# CH32F103R-R0.net
KiCad netlist of a schematic drawn in Altium Designer
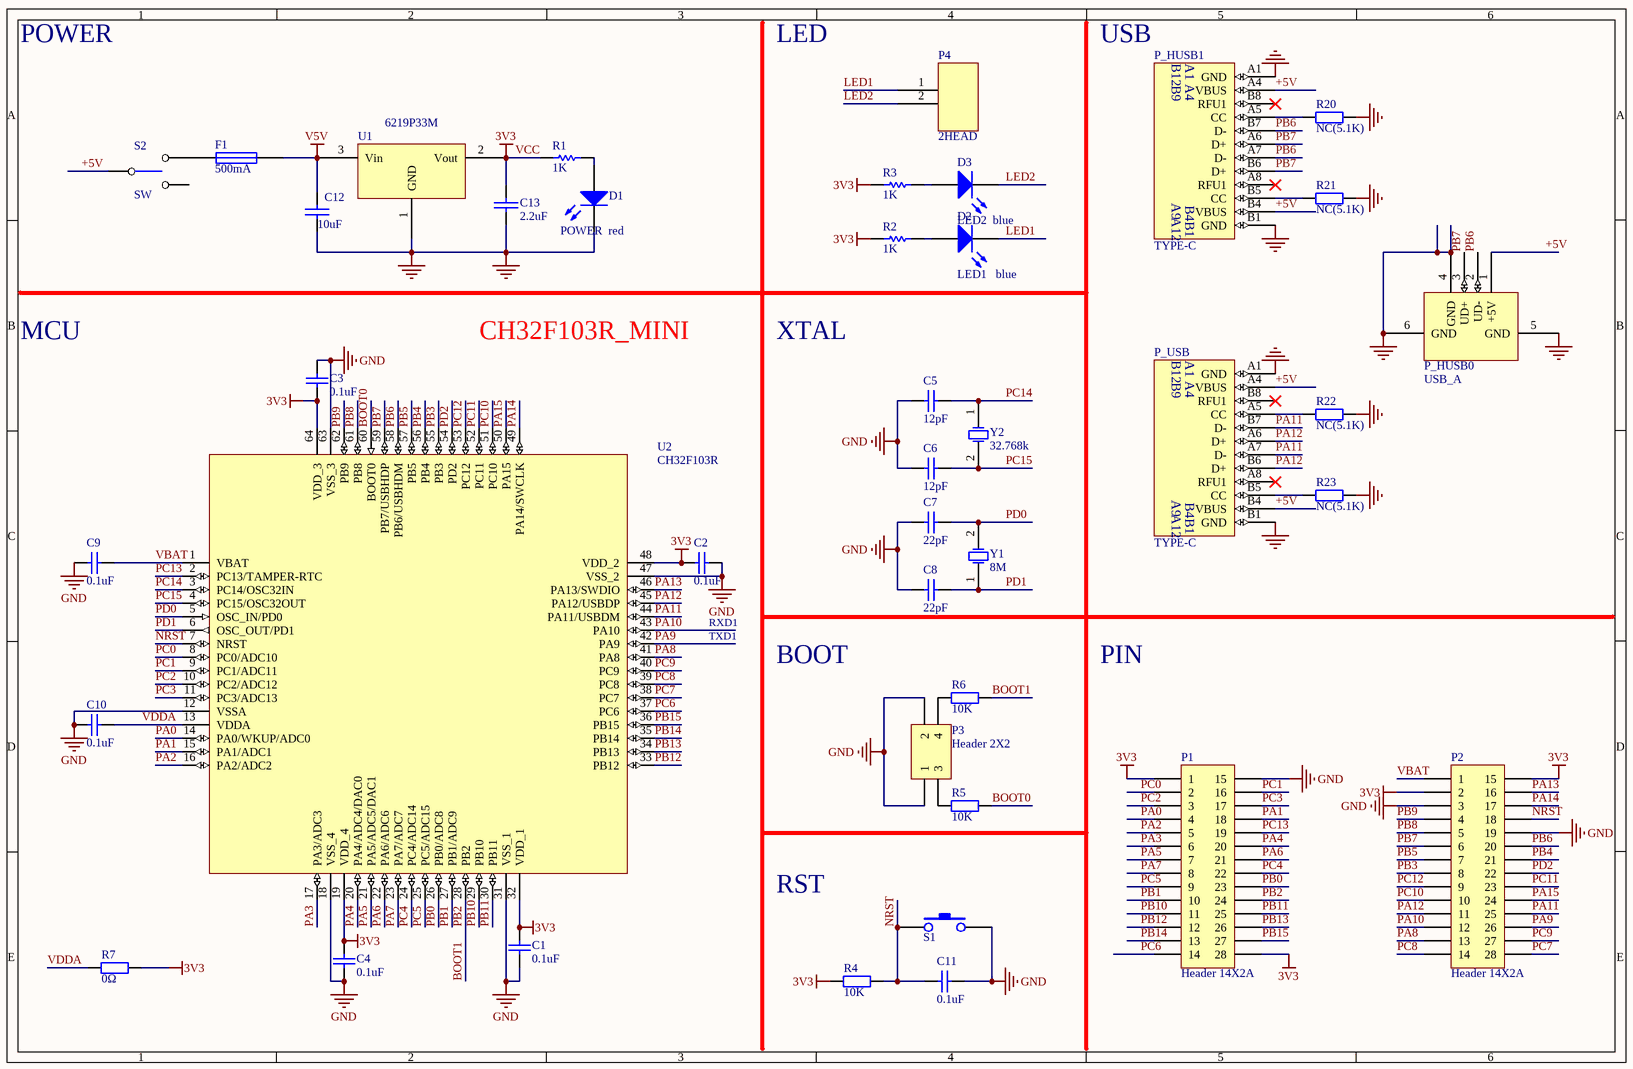
[diagram p0: CH32F103R-R0.SchDoc]

(export (version "E")
  (design (tool "Eeschema 10.0.6"))
  (components
    (comp (ref "C1")
      (value "0.1uF")
      (footprint "0603")
      (description "Capacitor")
      (fields (field (name "PUBLISHER") "Altium Limited"))
      (libsource (lib "Miscellaneous Devices") (part "Cap"))
    )
    (comp (ref "C2")
      (value "0.1uF")
      (footprint "0603")
      (description "Capacitor")
      (fields (field (name "PUBLISHER") "Altium Limited"))
      (libsource (lib "Miscellaneous Devices") (part "Cap"))
    )
    (comp (ref "C3")
      (value "0.1uF")
      (footprint "0603")
      (description "Capacitor")
      (fields (field (name "PUBLISHER") "Altium Limited"))
      (libsource (lib "Miscellaneous Devices") (part "Cap"))
    )
    (comp (ref "C4")
      (value "0.1uF")
      (footprint "0603")
      (description "Capacitor")
      (fields (field (name "PUBLISHER") "Altium Limited"))
      (libsource (lib "Miscellaneous Devices") (part "Cap"))
    )
    (comp (ref "C5")
      (value "12pF")
      (footprint "0603")
      (description "Capacitor")
      (fields (field (name "PUBLISHER") "Altium Limited"))
      (libsource (lib "Miscellaneous Devices") (part "Cap"))
    )
    (comp (ref "C6")
      (value "12pF")
      (footprint "0603")
      (description "Capacitor")
      (fields (field (name "PUBLISHER") "Altium Limited"))
      (libsource (lib "Miscellaneous Devices") (part "Cap"))
    )
    (comp (ref "C7")
      (value "22pF")
      (footprint "0603")
      (description "Capacitor")
      (fields (field (name "PUBLISHER") "Altium Limited"))
      (libsource (lib "Miscellaneous Devices") (part "Cap"))
    )
    (comp (ref "C8")
      (value "22pF")
      (footprint "0603")
      (description "Capacitor")
      (fields (field (name "PUBLISHER") "Altium Limited"))
      (libsource (lib "Miscellaneous Devices") (part "Cap"))
    )
    (comp (ref "C9")
      (value "0.1uF")
      (footprint "0603")
      (description "Capacitor")
      (fields (field (name "PUBLISHER") "Altium Limited"))
      (libsource (lib "Miscellaneous Devices") (part "Cap"))
    )
    (comp (ref "C10")
      (value "0.1uF")
      (footprint "0603")
      (description "Capacitor")
      (fields (field (name "PUBLISHER") "Altium Limited"))
      (libsource (lib "Miscellaneous Devices") (part "Cap"))
    )
    (comp (ref "C11")
      (value "0.1uF")
      (footprint "0603")
      (description "Capacitor")
      (fields (field (name "PUBLISHER") "Altium Limited"))
      (libsource (lib "Miscellaneous Devices") (part "Cap"))
    )
    (comp (ref "C12")
      (value "10uF")
      (footprint "3216")
      (description "Capacitor")
      (libsource (lib "*") (part "CAP"))
    )
    (comp (ref "C13")
      (value "2.2uF")
      (footprint "0603")
      (description "Capacitor")
      (libsource (lib "*") (part "CAP"))
    )
    (comp (ref "D1")
      (value "POWER  red")
      (footprint "0603L")
      (description "Typical INFRARED GaAs LED")
      (fields (field (name "PUBLISHER") "Altium Limited"))
      (libsource (lib "Miscellaneous Devices") (part "LED0"))
    )
    (comp (ref "D2")
      (value "LED1   blue")
      (footprint "0603L")
      (description "Typical INFRARED GaAs LED")
      (fields (field (name "PUBLISHER") "Altium Limited"))
      (libsource (lib "Miscellaneous Devices") (part "LED0"))
    )
    (comp (ref "D3")
      (value "LED2  blue")
      (footprint "0603L")
      (description "Typical INFRARED GaAs LED")
      (fields (field (name "PUBLISHER") "Altium Limited"))
      (libsource (lib "Miscellaneous Devices") (part "LED0"))
    )
    (comp (ref "F1")
      (value "500mA")
      (footprint "0603")
      (description "Fuse")
      (libsource (lib "*") (part "FUSE1"))
    )
    (comp (ref "P1")
      (value "Header 14X2A")
      (footprint "IDC28A")
      (description "Header, 14-Pin, Dual row")
      (fields (field (name "PUBLISHER") "Altium Limited"))
      (libsource (lib "Miscellaneous Connectors") (part "Header 14X2A"))
    )
    (comp (ref "P2")
      (value "Header 14X2A")
      (footprint "IDC28A")
      (description "Header, 14-Pin, Dual row")
      (fields (field (name "PUBLISHER") "Altium Limited"))
      (libsource (lib "Miscellaneous Connectors") (part "Header 14X2A"))
    )
    (comp (ref "P3")
      (value "Header 2X2")
      (footprint "HDR2X2")
      (description "Header, 2-Pin, Dual row")
      (fields (field (name "PUBLISHER") "Altium Limited"))
      (libsource (lib "Miscellaneous Connectors") (part "Header 2X2"))
    )
    (comp (ref "P4") (value "2HEAD") (footprint "SIP2 - 40mil") (libsource (lib "MYSCH") (part "2HEAD")))
    (comp (ref "P_HUSB0")
      (value "USB_A")
      (footprint "USBA-l")
      (description "USB Port")
      (libsource (lib "CHXXXSCH") (part "USB"))
    )
    (comp (ref "P_HUSB1")
      (value "TYPE-C")
      (footprint "TYPE-C-Receptacle-2.0")
      (libsource (lib "*") (part "TYPE-C1"))
    )
    (comp (ref "P_USB")
      (value "TYPE-C")
      (footprint "TYPE-C-Receptacle-2.0")
      (libsource (lib "*") (part "TYPE-C1"))
    )
    (comp (ref "R1")
      (value "1K")
      (footprint "0603")
      (description "Semiconductor Resistor")
      (fields (field (name "PUBLISHER") "Altium Limited"))
      (libsource (lib "Miscellaneous Devices") (part "Res Semi"))
    )
    (comp (ref "R2")
      (value "1K")
      (footprint "0603")
      (description "Semiconductor Resistor")
      (fields (field (name "PUBLISHER") "Altium Limited"))
      (libsource (lib "Miscellaneous Devices") (part "Res Semi"))
    )
    (comp (ref "R3")
      (value "1K")
      (footprint "0603")
      (description "Semiconductor Resistor")
      (fields (field (name "PUBLISHER") "Altium Limited"))
      (libsource (lib "Miscellaneous Devices") (part "Res Semi"))
    )
    (comp (ref "R4")
      (value "10K")
      (footprint "0603")
      (description "Resistor")
      (fields (field (name "PUBLISHER") "Altium Limited"))
      (libsource (lib "Miscellaneous Devices") (part "Res2"))
    )
    (comp (ref "R5")
      (value "10K")
      (footprint "0603")
      (description "Resistor")
      (fields (field (name "PUBLISHER") "Altium Limited"))
      (libsource (lib "Miscellaneous Devices") (part "Res2"))
    )
    (comp (ref "R6")
      (value "10K")
      (footprint "0603")
      (description "Resistor")
      (fields (field (name "PUBLISHER") "Altium Limited"))
      (libsource (lib "Miscellaneous Devices") (part "Res2"))
    )
    (comp (ref "R7")
      (value "0Ω")
      (footprint "0603")
      (description "Resistor")
      (fields (field (name "PUBLISHER") "Altium Limited"))
      (libsource (lib "Miscellaneous Devices") (part "Res2"))
    )
    (comp (ref "R20")
      (value "NC(5.1K)")
      (footprint "0603")
      (description "Resistor")
      (libsource (lib "") (part "Res2_1"))
    )
    (comp (ref "R21")
      (value "NC(5.1K)")
      (footprint "0603")
      (description "Resistor")
      (libsource (lib "") (part "Res2_1"))
    )
    (comp (ref "R22")
      (value "NC(5.1K)")
      (footprint "0603")
      (description "Resistor")
      (libsource (lib "") (part "Res2_1"))
    )
    (comp (ref "R23")
      (value "NC(5.1K)")
      (footprint "0603")
      (description "Resistor")
      (libsource (lib "") (part "Res2_1"))
    )
    (comp (ref "S1") (value "KEY") (footprint "贴片按键") (libsource (lib "CCDXPLIB") (part "KEY")))
    (comp (ref "S2") (value "SW") (footprint "KEY2") (libsource (lib "MYSCH") (part "SW")))
    (comp (ref "U1")
      (value "6219P33M")
      (footprint "SOT-23")
      (libsource (lib "wch_sch_others") (part "6219P33M"))
    )
    (comp (ref "U2")
      (value "CH32F103R")
      (footprint "LQFP64M_10X10")
      (description "ARM M3 MCU with USB device & USB host & ADC & 12bit DAC & Touch Key & CAN")
      (libsource (lib "CHXXX") (part "CH32F103R"))
    )
    (comp (ref "Y1")
      (value "8M")
      (footprint "XT62/28")
      (description "Crystal Oscillator")
      (fields (field (name "PUBLISHER") "Altium Limited"))
      (libsource (lib "Miscellaneous Devices") (part "XTAL"))
    )
    (comp (ref "Y2")
      (value "32.768k")
      (footprint "FC-135")
      (description "Crystal Oscillator")
      (fields (field (name "PUBLISHER") "Altium Limited"))
      (libsource (lib "Miscellaneous Devices") (part "XTAL"))
    )
  )
  (nets
    (net (code "1") (name "/+5V") (class "Default")
      (node (ref "P_HUSB0") (pin "1") (pinfunction "+5V_1") (pintype "power_in"))
      (node (ref "P_HUSB1") (pin "A4") (pinfunction "VBUS_A4") (pintype "bidirectional"))
      (node (ref "P_HUSB1") (pin "B4") (pinfunction "VBUS_B4") (pintype "bidirectional"))
      (node (ref "P_USB") (pin "A4") (pinfunction "VBUS_A4") (pintype "bidirectional"))
      (node (ref "P_USB") (pin "B4") (pinfunction "VBUS_B4") (pintype "bidirectional"))
      (node (ref "S2") (pin "1") (pinfunction "1_1") (pintype "passive"))
    )
    (net (code "3") (name "/BOOT0") (class "Default")
      (node (ref "R5") (pin "1") (pinfunction "1_1") (pintype "passive"))
      (node (ref "U2") (pin "60") (pinfunction "BOOT0_60") (pintype "input"))
    )
    (net (code "4") (name "/BOOT1") (class "Default")
      (node (ref "P1") (pin "24") (pinfunction "24_24") (pintype "passive"))
      (node (ref "R6") (pin "1") (pinfunction "1_1") (pintype "passive"))
      (node (ref "U2") (pin "28") (pinfunction "PB2_28") (pintype "bidirectional"))
    )
    (net (code "5") (name "/LED1") (class "Default")
      (node (ref "D2") (pin "2") (pinfunction "K_2") (pintype "passive"))
      (node (ref "P4") (pin "1") (pintype "passive"))
    )
    (net (code "6") (name "/LED2") (class "Default")
      (node (ref "D3") (pin "2") (pinfunction "K_2") (pintype "passive"))
      (node (ref "P4") (pin "2") (pintype "passive"))
    )
    (net (code "7") (name "/NRST") (class "Default")
      (node (ref "C11") (pin "2") (pinfunction "2_2") (pintype "passive"))
      (node (ref "P2") (pin "18") (pinfunction "18_18") (pintype "passive"))
      (node (ref "R4") (pin "1") (pinfunction "1_1") (pintype "passive"))
      (node (ref "S1") (pin "1") (pinfunction "1_1") (pintype "passive"))
      (node (ref "U2") (pin "7") (pinfunction "NRST_7") (pintype "bidirectional"))
    )
    (net (code "8") (name "/PA0") (class "Default")
      (node (ref "P1") (pin "4") (pinfunction "4_4") (pintype "passive"))
      (node (ref "U2") (pin "14") (pinfunction "PA0/WKUP/ADC0_14") (pintype "bidirectional"))
    )
    (net (code "9") (name "/PA1") (class "Default")
      (node (ref "P1") (pin "18") (pinfunction "18_18") (pintype "passive"))
      (node (ref "U2") (pin "15") (pinfunction "PA1/ADC1_15") (pintype "bidirectional"))
    )
    (net (code "10") (name "/PA2") (class "Default")
      (node (ref "P1") (pin "5") (pinfunction "5_5") (pintype "passive"))
      (node (ref "U2") (pin "16") (pinfunction "PA2/ADC2_16") (pintype "bidirectional"))
    )
    (net (code "11") (name "/PA3") (class "Default")
      (node (ref "P1") (pin "6") (pinfunction "6_6") (pintype "passive"))
      (node (ref "U2") (pin "17") (pinfunction "PA3/ADC3_17") (pintype "bidirectional"))
    )
    (net (code "12") (name "/PA4") (class "Default")
      (node (ref "P1") (pin "20") (pinfunction "20_20") (pintype "passive"))
      (node (ref "U2") (pin "20") (pinfunction "PA4/ADC4/DAC0_20") (pintype "bidirectional"))
    )
    (net (code "13") (name "/PA5") (class "Default")
      (node (ref "P1") (pin "7") (pinfunction "7_7") (pintype "passive"))
      (node (ref "U2") (pin "21") (pinfunction "PA5/ADC5/DAC1_21") (pintype "bidirectional"))
    )
    (net (code "14") (name "/PA6") (class "Default")
      (node (ref "P1") (pin "21") (pinfunction "21_21") (pintype "passive"))
      (node (ref "U2") (pin "22") (pinfunction "PA6/ADC6_22") (pintype "bidirectional"))
    )
    (net (code "15") (name "/PA7") (class "Default")
      (node (ref "P1") (pin "8") (pinfunction "8_8") (pintype "passive"))
      (node (ref "U2") (pin "23") (pinfunction "PA7/ADC7_23") (pintype "bidirectional"))
    )
    (net (code "16") (name "/PA8") (class "Default")
      (node (ref "P2") (pin "13") (pinfunction "13_13") (pintype "passive"))
      (node (ref "U2") (pin "41") (pinfunction "PA8_41") (pintype "bidirectional"))
    )
    (net (code "17") (name "/PA9") (class "Default")
      (node (ref "P2") (pin "26") (pinfunction "26_26") (pintype "passive"))
      (node (ref "U2") (pin "42") (pinfunction "PA9_42") (pintype "bidirectional"))
    )
    (net (code "18") (name "/PA10") (class "Default")
      (node (ref "P2") (pin "12") (pinfunction "12_12") (pintype "passive"))
      (node (ref "U2") (pin "43") (pinfunction "PA10_43") (pintype "bidirectional"))
    )
    (net (code "19") (name "/PA11") (class "Default")
      (node (ref "P2") (pin "25") (pinfunction "25_25") (pintype "passive"))
      (node (ref "P_USB") (pin "A7") (pinfunction "D-_A7") (pintype "bidirectional"))
      (node (ref "P_USB") (pin "B7") (pinfunction "D-_B7") (pintype "bidirectional"))
      (node (ref "U2") (pin "44") (pinfunction "PA11/USBDM_44") (pintype "bidirectional"))
    )
    (net (code "20") (name "/PA12") (class "Default")
      (node (ref "P2") (pin "11") (pinfunction "11_11") (pintype "passive"))
      (node (ref "P_USB") (pin "A6") (pinfunction "D+_A6") (pintype "bidirectional"))
      (node (ref "P_USB") (pin "B6") (pinfunction "D+_B6") (pintype "bidirectional"))
      (node (ref "U2") (pin "45") (pinfunction "PA12/USBDP_45") (pintype "bidirectional"))
    )
    (net (code "21") (name "/PA13") (class "Default")
      (node (ref "P2") (pin "16") (pinfunction "16_16") (pintype "passive"))
      (node (ref "U2") (pin "46") (pinfunction "PA13/SWDIO_46") (pintype "bidirectional"))
    )
    (net (code "22") (name "/PA14") (class "Default")
      (node (ref "P2") (pin "17") (pinfunction "17_17") (pintype "passive"))
      (node (ref "U2") (pin "49") (pinfunction "PA14/SWCLK_49") (pintype "bidirectional"))
    )
    (net (code "23") (name "/PA15") (class "Default")
      (node (ref "P2") (pin "24") (pinfunction "24_24") (pintype "passive"))
      (node (ref "U2") (pin "50") (pinfunction "PA15_50") (pintype "bidirectional"))
    )
    (net (code "24") (name "/PB0") (class "Default")
      (node (ref "P1") (pin "23") (pinfunction "23_23") (pintype "passive"))
      (node (ref "U2") (pin "26") (pinfunction "PB0/ADC8_26") (pintype "bidirectional"))
    )
    (net (code "25") (name "/PB1") (class "Default")
      (node (ref "P1") (pin "10") (pinfunction "10_10") (pintype "passive"))
      (node (ref "U2") (pin "27") (pinfunction "PB1/ADC9_27") (pintype "bidirectional"))
    )
    (net (code "26") (name "/PB3") (class "Default")
      (node (ref "P2") (pin "8") (pinfunction "8_8") (pintype "passive"))
      (node (ref "U2") (pin "55") (pinfunction "PB3_55") (pintype "bidirectional"))
    )
    (net (code "27") (name "/PB4") (class "Default")
      (node (ref "P2") (pin "21") (pinfunction "21_21") (pintype "passive"))
      (node (ref "U2") (pin "56") (pinfunction "PB4_56") (pintype "bidirectional"))
    )
    (net (code "28") (name "/PB5") (class "Default")
      (node (ref "P2") (pin "7") (pinfunction "7_7") (pintype "passive"))
      (node (ref "U2") (pin "57") (pinfunction "PB5_57") (pintype "bidirectional"))
    )
    (net (code "29") (name "/PB6") (class "Default")
      (node (ref "P2") (pin "20") (pinfunction "20_20") (pintype "passive"))
      (node (ref "P_HUSB0") (pin "2") (pinfunction "UD-_2") (pintype "bidirectional"))
      (node (ref "P_HUSB1") (pin "A7") (pinfunction "D-_A7") (pintype "bidirectional"))
      (node (ref "P_HUSB1") (pin "B7") (pinfunction "D-_B7") (pintype "bidirectional"))
      (node (ref "U2") (pin "58") (pinfunction "PB6/USBHDM_58") (pintype "bidirectional"))
    )
    (net (code "30") (name "/PB7") (class "Default")
      (node (ref "P2") (pin "6") (pinfunction "6_6") (pintype "passive"))
      (node (ref "P_HUSB0") (pin "3") (pinfunction "UD+_3") (pintype "bidirectional"))
      (node (ref "P_HUSB1") (pin "A6") (pinfunction "D+_A6") (pintype "bidirectional"))
      (node (ref "P_HUSB1") (pin "B6") (pinfunction "D+_B6") (pintype "bidirectional"))
      (node (ref "U2") (pin "59") (pinfunction "PB7/USBHDP_59") (pintype "bidirectional"))
    )
    (net (code "31") (name "/PB8") (class "Default")
      (node (ref "P2") (pin "5") (pinfunction "5_5") (pintype "passive"))
      (node (ref "U2") (pin "61") (pinfunction "PB8_61") (pintype "bidirectional"))
    )
    (net (code "32") (name "/PB9") (class "Default")
      (node (ref "P2") (pin "4") (pinfunction "4_4") (pintype "passive"))
      (node (ref "U2") (pin "62") (pinfunction "PB9_62") (pintype "bidirectional"))
    )
    (net (code "33") (name "/PB10") (class "Default")
      (node (ref "P1") (pin "11") (pinfunction "11_11") (pintype "passive"))
      (node (ref "U2") (pin "29") (pinfunction "PB10_29") (pintype "bidirectional"))
    )
    (net (code "34") (name "/PB11") (class "Default")
      (node (ref "P1") (pin "25") (pinfunction "25_25") (pintype "passive"))
      (node (ref "U2") (pin "30") (pinfunction "PB11_30") (pintype "bidirectional"))
    )
    (net (code "35") (name "/PB12") (class "Default")
      (node (ref "P1") (pin "12") (pinfunction "12_12") (pintype "passive"))
      (node (ref "U2") (pin "33") (pinfunction "PB12_33") (pintype "bidirectional"))
    )
    (net (code "36") (name "/PB13") (class "Default")
      (node (ref "P1") (pin "26") (pinfunction "26_26") (pintype "passive"))
      (node (ref "U2") (pin "34") (pinfunction "PB13_34") (pintype "bidirectional"))
    )
    (net (code "37") (name "/PB14") (class "Default")
      (node (ref "P1") (pin "13") (pinfunction "13_13") (pintype "passive"))
      (node (ref "U2") (pin "35") (pinfunction "PB14_35") (pintype "bidirectional"))
    )
    (net (code "38") (name "/PB15") (class "Default")
      (node (ref "P1") (pin "27") (pinfunction "27_27") (pintype "passive"))
      (node (ref "U2") (pin "36") (pinfunction "PB15_36") (pintype "bidirectional"))
    )
    (net (code "39") (name "/PC0") (class "Default")
      (node (ref "P1") (pin "2") (pinfunction "2_2") (pintype "passive"))
      (node (ref "U2") (pin "8") (pinfunction "PC0/ADC10_8") (pintype "bidirectional"))
    )
    (net (code "40") (name "/PC1") (class "Default")
      (node (ref "P1") (pin "16") (pinfunction "16_16") (pintype "passive"))
      (node (ref "U2") (pin "9") (pinfunction "PC1/ADC11_9") (pintype "bidirectional"))
    )
    (net (code "41") (name "/PC2") (class "Default")
      (node (ref "P1") (pin "3") (pinfunction "3_3") (pintype "passive"))
      (node (ref "U2") (pin "10") (pinfunction "PC2/ADC12_10") (pintype "bidirectional"))
    )
    (net (code "42") (name "/PC3") (class "Default")
      (node (ref "P1") (pin "17") (pinfunction "17_17") (pintype "passive"))
      (node (ref "U2") (pin "11") (pinfunction "PC3/ADC13_11") (pintype "bidirectional"))
    )
    (net (code "43") (name "/PC4") (class "Default")
      (node (ref "P1") (pin "22") (pinfunction "22_22") (pintype "passive"))
      (node (ref "U2") (pin "24") (pinfunction "PC4/ADC14_24") (pintype "bidirectional"))
    )
    (net (code "44") (name "/PC5") (class "Default")
      (node (ref "P1") (pin "9") (pinfunction "9_9") (pintype "passive"))
      (node (ref "U2") (pin "25") (pinfunction "PC5/ADC15_25") (pintype "bidirectional"))
    )
    (net (code "45") (name "/PC6") (class "Default")
      (node (ref "P1") (pin "14") (pinfunction "14_14") (pintype "passive"))
      (node (ref "U2") (pin "37") (pinfunction "PC6_37") (pintype "bidirectional"))
    )
    (net (code "46") (name "/PC7") (class "Default")
      (node (ref "P2") (pin "28") (pinfunction "28_28") (pintype "passive"))
      (node (ref "U2") (pin "38") (pinfunction "PC7_38") (pintype "bidirectional"))
    )
    (net (code "47") (name "/PC8") (class "Default")
      (node (ref "P2") (pin "14") (pinfunction "14_14") (pintype "passive"))
      (node (ref "U2") (pin "39") (pinfunction "PC8_39") (pintype "bidirectional"))
    )
    (net (code "48") (name "/PC9") (class "Default")
      (node (ref "P2") (pin "27") (pinfunction "27_27") (pintype "passive"))
      (node (ref "U2") (pin "40") (pinfunction "PC9_40") (pintype "bidirectional"))
    )
    (net (code "49") (name "/PC10") (class "Default")
      (node (ref "P2") (pin "10") (pinfunction "10_10") (pintype "passive"))
      (node (ref "U2") (pin "51") (pinfunction "PC10_51") (pintype "bidirectional"))
    )
    (net (code "50") (name "/PC11") (class "Default")
      (node (ref "P2") (pin "23") (pinfunction "23_23") (pintype "passive"))
      (node (ref "U2") (pin "52") (pinfunction "PC11_52") (pintype "bidirectional"))
    )
    (net (code "51") (name "/PC12") (class "Default")
      (node (ref "P2") (pin "9") (pinfunction "9_9") (pintype "passive"))
      (node (ref "U2") (pin "53") (pinfunction "PC12_53") (pintype "bidirectional"))
    )
    (net (code "52") (name "/PC13") (class "Default")
      (node (ref "P1") (pin "19") (pinfunction "19_19") (pintype "passive"))
      (node (ref "U2") (pin "2") (pinfunction "PC13/TAMPER-RTC_2") (pintype "bidirectional"))
    )
    (net (code "53") (name "/PC14") (class "Default")
      (node (ref "C5") (pin "1") (pinfunction "1_1") (pintype "passive"))
      (node (ref "U2") (pin "3") (pinfunction "PC14/OSC32IN_3") (pintype "bidirectional"))
      (node (ref "Y2") (pin "1") (pinfunction "OSC1_1") (pintype "passive"))
    )
    (net (code "54") (name "/PC15") (class "Default")
      (node (ref "C6") (pin "1") (pinfunction "1_1") (pintype "passive"))
      (node (ref "U2") (pin "4") (pinfunction "PC15/OSC32OUT_4") (pintype "bidirectional"))
      (node (ref "Y2") (pin "2") (pinfunction "OSC2_2") (pintype "passive"))
    )
    (net (code "55") (name "/PD0") (class "Default")
      (node (ref "C7") (pin "2") (pinfunction "2_2") (pintype "passive"))
      (node (ref "U2") (pin "5") (pinfunction "OSC_IN/PD0_5") (pintype "input"))
      (node (ref "Y1") (pin "2") (pinfunction "OSC2_2") (pintype "passive"))
    )
    (net (code "56") (name "/PD1") (class "Default")
      (node (ref "C8") (pin "2") (pinfunction "2_2") (pintype "passive"))
      (node (ref "U2") (pin "6") (pinfunction "OSC_OUT/PD1_6") (pintype "output"))
      (node (ref "Y1") (pin "1") (pinfunction "OSC1_1") (pintype "passive"))
    )
    (net (code "57") (name "/PD2") (class "Default")
      (node (ref "P2") (pin "22") (pinfunction "22_22") (pintype "passive"))
      (node (ref "U2") (pin "54") (pinfunction "PD2_54") (pintype "bidirectional"))
    )
    (net (code "58") (name "/VBAT") (class "Default")
      (node (ref "C9") (pin "1") (pinfunction "1_1") (pintype "passive"))
      (node (ref "P2") (pin "1") (pinfunction "1_1") (pintype "passive"))
      (node (ref "U2") (pin "1") (pinfunction "VBAT_1") (pintype "power_in"))
    )
    (net (code "59") (name "/VDDA") (class "Default")
      (node (ref "C10") (pin "1") (pinfunction "1_1") (pintype "passive"))
      (node (ref "R7") (pin "2") (pinfunction "2_2") (pintype "passive"))
      (node (ref "U2") (pin "13") (pinfunction "VDDA_13") (pintype "power_in"))
    )
    (net (code "60") (name "3V3") (class "Default")
      (node (ref "C1") (pin "2") (pinfunction "2_2") (pintype "passive"))
      (node (ref "C13") (pin "1") (pinfunction "1_1") (pintype "passive"))
      (node (ref "C2") (pin "2") (pinfunction "2_2") (pintype "passive"))
      (node (ref "C3") (pin "2") (pinfunction "2_2") (pintype "passive"))
      (node (ref "C4") (pin "2") (pinfunction "2_2") (pintype "passive"))
      (node (ref "P1") (pin "1") (pinfunction "1_1") (pintype "passive"))
      (node (ref "P1") (pin "28") (pinfunction "28_28") (pintype "passive"))
      (node (ref "P2") (pin "15") (pinfunction "15_15") (pintype "passive"))
      (node (ref "P2") (pin "2") (pinfunction "2_2") (pintype "passive"))
      (node (ref "R1") (pin "2") (pinfunction "2_2") (pintype "passive"))
      (node (ref "R2") (pin "1") (pinfunction "1_1") (pintype "passive"))
      (node (ref "R3") (pin "1") (pinfunction "1_1") (pintype "passive"))
      (node (ref "R4") (pin "2") (pinfunction "2_2") (pintype "passive"))
      (node (ref "R7") (pin "1") (pinfunction "1_1") (pintype "passive"))
      (node (ref "U1") (pin "2") (pinfunction "Vout_2") (pintype "passive"))
      (node (ref "U2") (pin "19") (pinfunction "VDD_4_19") (pintype "power_in"))
      (node (ref "U2") (pin "32") (pinfunction "VDD_1_32") (pintype "power_in"))
      (node (ref "U2") (pin "48") (pinfunction "VDD_2_48") (pintype "power_in"))
      (node (ref "U2") (pin "64") (pinfunction "VDD_3_64") (pintype "power_in"))
    )
    (net (code "61") (name "GND") (class "Default")
      (node (ref "C1") (pin "1") (pinfunction "1_1") (pintype "passive"))
      (node (ref "C10") (pin "2") (pinfunction "2_2") (pintype "passive"))
      (node (ref "C11") (pin "1") (pinfunction "1_1") (pintype "passive"))
      (node (ref "C12") (pin "2") (pinfunction "2_2") (pintype "passive"))
      (node (ref "C13") (pin "2") (pinfunction "2_2") (pintype "passive"))
      (node (ref "C2") (pin "1") (pinfunction "1_1") (pintype "passive"))
      (node (ref "C3") (pin "1") (pinfunction "1_1") (pintype "passive"))
      (node (ref "C4") (pin "1") (pinfunction "1_1") (pintype "passive"))
      (node (ref "C5") (pin "2") (pinfunction "2_2") (pintype "passive"))
      (node (ref "C6") (pin "2") (pinfunction "2_2") (pintype "passive"))
      (node (ref "C7") (pin "1") (pinfunction "1_1") (pintype "passive"))
      (node (ref "C8") (pin "1") (pinfunction "1_1") (pintype "passive"))
      (node (ref "C9") (pin "2") (pinfunction "2_2") (pintype "passive"))
      (node (ref "D1") (pin "2") (pinfunction "K_2") (pintype "passive"))
      (node (ref "P1") (pin "15") (pinfunction "15_15") (pintype "passive"))
      (node (ref "P2") (pin "19") (pinfunction "19_19") (pintype "passive"))
      (node (ref "P2") (pin "3") (pinfunction "3_3") (pintype "passive"))
      (node (ref "P3") (pin "1") (pinfunction "1_1") (pintype "passive"))
      (node (ref "P3") (pin "2") (pinfunction "2_2") (pintype "passive"))
      (node (ref "P_HUSB0") (pin "4") (pinfunction "GND_4") (pintype "power_in"))
      (node (ref "P_HUSB0") (pin "5") (pinfunction "GND_5") (pintype "power_in"))
      (node (ref "P_HUSB0") (pin "6") (pinfunction "GND_6") (pintype "power_in"))
      (node (ref "P_HUSB1") (pin "A1") (pinfunction "GND_A1") (pintype "bidirectional"))
      (node (ref "P_HUSB1") (pin "B1") (pinfunction "GND_B1") (pintype "bidirectional"))
      (node (ref "P_USB") (pin "A1") (pinfunction "GND_A1") (pintype "bidirectional"))
      (node (ref "P_USB") (pin "B1") (pinfunction "GND_B1") (pintype "bidirectional"))
      (node (ref "R20") (pin "2") (pinfunction "2_2") (pintype "passive"))
      (node (ref "R21") (pin "2") (pinfunction "2_2") (pintype "passive"))
      (node (ref "R22") (pin "2") (pinfunction "2_2") (pintype "passive"))
      (node (ref "R23") (pin "2") (pinfunction "2_2") (pintype "passive"))
      (node (ref "S1") (pin "3") (pinfunction "3_3") (pintype "passive"))
      (node (ref "U1") (pin "1") (pinfunction "GND_1") (pintype "passive"))
      (node (ref "U2") (pin "12") (pinfunction "VSSA_12") (pintype "power_in"))
      (node (ref "U2") (pin "18") (pinfunction "VSS_4_18") (pintype "power_in"))
      (node (ref "U2") (pin "31") (pinfunction "VSS_1_31") (pintype "power_in"))
      (node (ref "U2") (pin "47") (pinfunction "VSS_2_47") (pintype "power_in"))
      (node (ref "U2") (pin "63") (pinfunction "VSS_3_63") (pintype "power_in"))
    )
    (net (code "62") (name "Net-(D1-A)") (class "Default")
      (node (ref "D1") (pin "1") (pinfunction "A_1") (pintype "passive"))
      (node (ref "R1") (pin "1") (pinfunction "1_1") (pintype "passive"))
    )
    (net (code "63") (name "Net-(D2-A)") (class "Default")
      (node (ref "D2") (pin "1") (pinfunction "A_1") (pintype "passive"))
      (node (ref "R2") (pin "2") (pinfunction "2_2") (pintype "passive"))
    )
    (net (code "64") (name "Net-(D3-A)") (class "Default")
      (node (ref "D3") (pin "1") (pinfunction "A_1") (pintype "passive"))
      (node (ref "R3") (pin "2") (pinfunction "2_2") (pintype "passive"))
    )
    (net (code "65") (name "Net-(F1-Pad1)") (class "Default")
      (node (ref "F1") (pin "1") (pinfunction "1_1") (pintype "passive"))
      (node (ref "S2") (pin "3") (pinfunction "3_3") (pintype "passive"))
    )
    (net (code "66") (name "Net-(P3-Pad3)") (class "Default")
      (node (ref "P3") (pin "3") (pinfunction "3_3") (pintype "passive"))
      (node (ref "R5") (pin "2") (pinfunction "2_2") (pintype "passive"))
    )
    (net (code "67") (name "Net-(P3-Pad4)") (class "Default")
      (node (ref "P3") (pin "4") (pinfunction "4_4") (pintype "passive"))
      (node (ref "R6") (pin "2") (pinfunction "2_2") (pintype "passive"))
    )
    (net (code "68") (name "Net-(P_HUSB1-CC-PadA5)") (class "Default")
      (node (ref "P_HUSB1") (pin "A5") (pinfunction "CC_A5") (pintype "bidirectional"))
      (node (ref "R20") (pin "1") (pinfunction "1_1") (pintype "passive"))
    )
    (net (code "69") (name "Net-(P_HUSB1-CC-PadB5)") (class "Default")
      (node (ref "P_HUSB1") (pin "B5") (pinfunction "CC_B5") (pintype "bidirectional"))
      (node (ref "R21") (pin "1") (pinfunction "1_1") (pintype "passive"))
    )
    (net (code "70") (name "Net-(P_USB-CC-PadA5)") (class "Default")
      (node (ref "P_USB") (pin "A5") (pinfunction "CC_A5") (pintype "bidirectional"))
      (node (ref "R22") (pin "1") (pinfunction "1_1") (pintype "passive"))
    )
    (net (code "71") (name "Net-(P_USB-CC-PadB5)") (class "Default")
      (node (ref "P_USB") (pin "B5") (pinfunction "CC_B5") (pintype "bidirectional"))
      (node (ref "R23") (pin "1") (pinfunction "1_1") (pintype "passive"))
    )
    (net (code "72") (name "V5V") (class "Default")
      (node (ref "C12") (pin "1") (pinfunction "1_1") (pintype "passive"))
      (node (ref "F1") (pin "2") (pinfunction "2_2") (pintype "passive"))
      (node (ref "U1") (pin "3") (pinfunction "Vin_3") (pintype "passive"))
    )
    (net (code "73") (name "unconnected-(P_HUSB1-RFU1-PadA8)") (class "Default")
      (node (ref "P_HUSB1") (pin "A8") (pinfunction "RFU1_A8") (pintype "bidirectional+no_connect"))
    )
    (net (code "74") (name "unconnected-(P_HUSB1-RFU1-PadB8)") (class "Default")
      (node (ref "P_HUSB1") (pin "B8") (pinfunction "RFU1_B8") (pintype "bidirectional+no_connect"))
    )
    (net (code "75") (name "unconnected-(P_USB-RFU1-PadA8)") (class "Default")
      (node (ref "P_USB") (pin "A8") (pinfunction "RFU1_A8") (pintype "bidirectional+no_connect"))
    )
    (net (code "76") (name "unconnected-(P_USB-RFU1-PadB8)") (class "Default")
      (node (ref "P_USB") (pin "B8") (pinfunction "RFU1_B8") (pintype "bidirectional+no_connect"))
    )
    (net (code "77") (name "unconnected-(S2-Pad2)") (class "Default")
      (node (ref "S2") (pin "2") (pinfunction "2_2") (pintype "passive"))
    )
  )
)
